# 2_-_Connector_Page.net
KiCad netlist of a schematic drawn in Altium Designer
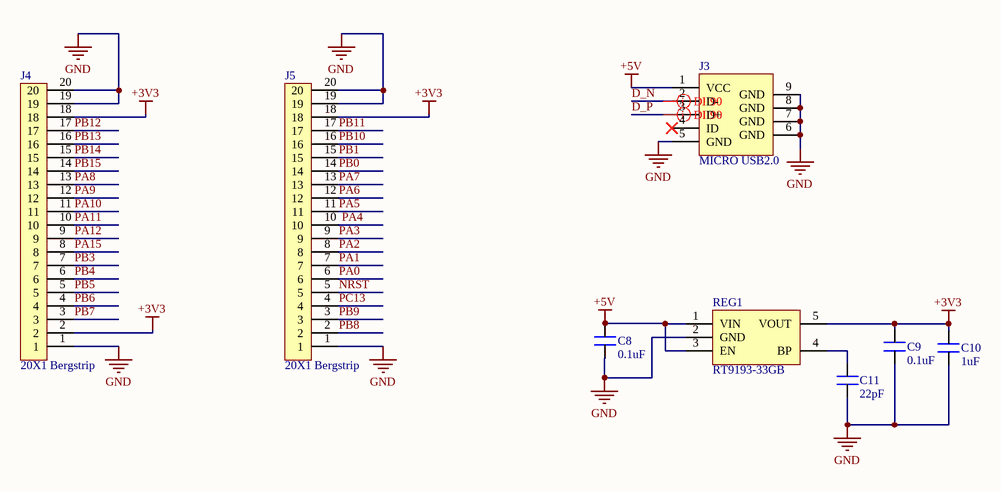
[diagram p0: [2]- Connector_Page.SchDoc]

(export (version "E")
  (design (tool "Eeschema 10.0.6"))
  (components
    (comp (ref "C8")
      (value "0.1uF")
      (footprint "CAP_0805")
      (description "0.1µF ±5% 50V Ceramic Capacitor X7R 0805 (2012 Metric)")
      (fields
        (field (name "MANUFACTURER") "KEMET")
        (field (name "MANUFACTURING PART NUMBER") "C0805C104J5RACTU")
      )
      (libsource (lib "STM_SCH_LIB") (part "CAP_0.1uF-50V-5%-0805"))
    )
    (comp (ref "C9")
      (value "0.1uF")
      (footprint "CAP_0805")
      (description "0.1µF ±5% 50V Ceramic Capacitor X7R 0805 (2012 Metric)")
      (fields
        (field (name "MANUFACTURER") "KEMET")
        (field (name "MANUFACTURING PART NUMBER") "C0805C104J5RACTU")
      )
      (libsource (lib "STM_SCH_LIB") (part "CAP_0.1uF-50V-5%-0805"))
    )
    (comp (ref "C10")
      (value "1uF")
      (footprint "CAP_0805")
      (description "1µF ±5% 50V Ceramic Capacitor X7R 0805 (2012 Metric)")
      (fields
        (field (name "MANUFACTURER") "Yageo")
        (field (name "MANUFACTURING PART NUMBER") "CC0805JKX7R9BB105")
      )
      (libsource (lib "STM_SCH_LIB") (part "CAP_1uF-50V-5%-0805"))
    )
    (comp (ref "C11")
      (value "22pF")
      (footprint "CAP_0805")
      (description "22pF ±5% 50V Ceramic Capacitor C0G, NP0 0805 (2012 Metric)")
      (fields
        (field (name "MANUFACTURER") "KEMET")
        (field (name "MANUFACTURER PART NUMBER") "C0805C220J5GACTU")
      )
      (libsource (lib "STM_SCH_LIB") (part "CAP_22pF-50V-5%-0805"))
    )
    (comp (ref "J3")
      (value "MICRO USB2.0")
      (footprint "CON_10118192-0001LF_SMD")
      (description "USB - micro B USB 2.0 Receptacle Connector 5 Position Surface Mount, Right Angle")
      (fields
        (field (name "MANUFACTURER") "Amphenol ICC (FCI)")
        (field (name "MANUFACTURING PART NUMBER") "10118192-0002LF")
      )
      (libsource (lib "STM_SCH_LIB") (part "CON-USB_10118192-0002LF-SMD"))
    )
    (comp (ref "J4")
      (value "20X1 Bergstrip")
      (footprint "CON20_100_40D72_TH_ST")
      (description "20 pin, 1 row, 2.54mm pitch bergstrip")
      (fields (field (name "MANUFACTURER") "NA"))
      (libsource (lib "STM_SCH_LIB") (part "CON-BS-PLG_20X1-100-TH-ST"))
    )
    (comp (ref "J5")
      (value "20X1 Bergstrip")
      (footprint "CON20_100_40D72_TH_ST")
      (description "20 pin, 1 row, 2.54mm pitch bergstrip")
      (fields (field (name "MANUFACTURER") "NA"))
      (libsource (lib "STM_SCH_LIB") (part "CON-BS-PLG_20X1-100-TH-ST"))
    )
    (comp (ref "REG1")
      (value "RT9193-33GB")
      (footprint "SOT23-5")
      (description "Linear Voltage Regulator IC 1 Output 300mA SOT-23-5")
      (fields (field (name "MANUFACTURER") "Richtek USA Inc."))
      (libsource (lib "STM_SCH_LIB") (part "REG_3.3V-5.5V-0.3A-SOT-23-5"))
    )
  )
  (nets
    (net (code "1") (name "+3V3") (class "Default")
      (node (ref "C10") (pin "2") (pinfunction "2_2") (pintype "passive"))
      (node (ref "C9") (pin "2") (pinfunction "2_2") (pintype "passive"))
      (node (ref "J4") (pin "18") (pinfunction "18_18") (pintype "passive"))
      (node (ref "J4") (pin "2") (pinfunction "2_2") (pintype "passive"))
      (node (ref "J5") (pin "18") (pinfunction "18_18") (pintype "passive"))
      (node (ref "REG1") (pin "5") (pinfunction "VOUT_5") (pintype "passive"))
    )
    (net (code "2") (name "+5V") (class "Default")
      (node (ref "C8") (pin "2") (pinfunction "2_2") (pintype "passive"))
      (node (ref "J3") (pin "1") (pinfunction "VCC_1") (pintype "passive"))
      (node (ref "REG1") (pin "1") (pinfunction "VIN_1") (pintype "passive"))
      (node (ref "REG1") (pin "3") (pinfunction "EN_3") (pintype "passive"))
    )
    (net (code "3") (name "/D_N") (class "Default")
      (node (ref "J3") (pin "2") (pinfunction "D-_2") (pintype "passive"))
    )
    (net (code "4") (name "/D_P") (class "Default")
      (node (ref "J3") (pin "3") (pinfunction "D+_3") (pintype "passive"))
    )
    (net (code "5") (name "/NRST") (class "Default")
      (node (ref "J5") (pin "5") (pinfunction "5_5") (pintype "passive"))
    )
    (net (code "6") (name "/PA0") (class "Default")
      (node (ref "J5") (pin "6") (pinfunction "6_6") (pintype "passive"))
    )
    (net (code "7") (name "/PA1") (class "Default")
      (node (ref "J5") (pin "7") (pinfunction "7_7") (pintype "passive"))
    )
    (net (code "8") (name "/PA2") (class "Default")
      (node (ref "J5") (pin "8") (pinfunction "8_8") (pintype "passive"))
    )
    (net (code "9") (name "/PA3") (class "Default")
      (node (ref "J5") (pin "9") (pinfunction "9_9") (pintype "passive"))
    )
    (net (code "10") (name "/PA4") (class "Default")
      (node (ref "J5") (pin "10") (pinfunction "10_10") (pintype "passive"))
    )
    (net (code "11") (name "/PA5") (class "Default")
      (node (ref "J5") (pin "11") (pinfunction "11_11") (pintype "passive"))
    )
    (net (code "12") (name "/PA6") (class "Default")
      (node (ref "J5") (pin "12") (pinfunction "12_12") (pintype "passive"))
    )
    (net (code "13") (name "/PA7") (class "Default")
      (node (ref "J5") (pin "13") (pinfunction "13_13") (pintype "passive"))
    )
    (net (code "14") (name "/PA8") (class "Default")
      (node (ref "J4") (pin "13") (pinfunction "13_13") (pintype "passive"))
    )
    (net (code "15") (name "/PA9") (class "Default")
      (node (ref "J4") (pin "12") (pinfunction "12_12") (pintype "passive"))
    )
    (net (code "16") (name "/PA10") (class "Default")
      (node (ref "J4") (pin "11") (pinfunction "11_11") (pintype "passive"))
    )
    (net (code "17") (name "/PA11") (class "Default")
      (node (ref "J4") (pin "10") (pinfunction "10_10") (pintype "passive"))
    )
    (net (code "18") (name "/PA12") (class "Default")
      (node (ref "J4") (pin "9") (pinfunction "9_9") (pintype "passive"))
    )
    (net (code "19") (name "/PA15") (class "Default")
      (node (ref "J4") (pin "8") (pinfunction "8_8") (pintype "passive"))
    )
    (net (code "20") (name "/PB0") (class "Default")
      (node (ref "J5") (pin "14") (pinfunction "14_14") (pintype "passive"))
    )
    (net (code "21") (name "/PB1") (class "Default")
      (node (ref "J5") (pin "15") (pinfunction "15_15") (pintype "passive"))
    )
    (net (code "22") (name "/PB3") (class "Default")
      (node (ref "J4") (pin "7") (pinfunction "7_7") (pintype "passive"))
    )
    (net (code "23") (name "/PB4") (class "Default")
      (node (ref "J4") (pin "6") (pinfunction "6_6") (pintype "passive"))
    )
    (net (code "24") (name "/PB5") (class "Default")
      (node (ref "J4") (pin "5") (pinfunction "5_5") (pintype "passive"))
    )
    (net (code "25") (name "/PB6") (class "Default")
      (node (ref "J4") (pin "4") (pinfunction "4_4") (pintype "passive"))
    )
    (net (code "26") (name "/PB7") (class "Default")
      (node (ref "J4") (pin "3") (pinfunction "3_3") (pintype "passive"))
    )
    (net (code "27") (name "/PB8") (class "Default")
      (node (ref "J5") (pin "2") (pinfunction "2_2") (pintype "passive"))
    )
    (net (code "28") (name "/PB9") (class "Default")
      (node (ref "J5") (pin "3") (pinfunction "3_3") (pintype "passive"))
    )
    (net (code "29") (name "/PB10") (class "Default")
      (node (ref "J5") (pin "16") (pinfunction "16_16") (pintype "passive"))
    )
    (net (code "30") (name "/PB11") (class "Default")
      (node (ref "J5") (pin "17") (pinfunction "17_17") (pintype "passive"))
    )
    (net (code "31") (name "/PB12") (class "Default")
      (node (ref "J4") (pin "17") (pinfunction "17_17") (pintype "passive"))
    )
    (net (code "32") (name "/PB13") (class "Default")
      (node (ref "J4") (pin "16") (pinfunction "16_16") (pintype "passive"))
    )
    (net (code "33") (name "/PB14") (class "Default")
      (node (ref "J4") (pin "15") (pinfunction "15_15") (pintype "passive"))
    )
    (net (code "34") (name "/PB15") (class "Default")
      (node (ref "J4") (pin "14") (pinfunction "14_14") (pintype "passive"))
    )
    (net (code "35") (name "/PC13") (class "Default")
      (node (ref "J5") (pin "4") (pinfunction "4_4") (pintype "passive"))
    )
    (net (code "36") (name "GND") (class "Default")
      (node (ref "C10") (pin "1") (pinfunction "1_1") (pintype "passive"))
      (node (ref "C11") (pin "1") (pinfunction "1_1") (pintype "passive"))
      (node (ref "C8") (pin "1") (pinfunction "1_1") (pintype "passive"))
      (node (ref "C9") (pin "1") (pinfunction "1_1") (pintype "passive"))
      (node (ref "J3") (pin "5") (pinfunction "GND_5") (pintype "passive"))
      (node (ref "J3") (pin "6") (pinfunction "GND_6") (pintype "passive"))
      (node (ref "J3") (pin "7") (pinfunction "GND_7") (pintype "passive"))
      (node (ref "J3") (pin "8") (pinfunction "GND_8") (pintype "passive"))
      (node (ref "J3") (pin "9") (pinfunction "GND_9") (pintype "passive"))
      (node (ref "J4") (pin "1") (pinfunction "1_1") (pintype "passive"))
      (node (ref "J4") (pin "19") (pinfunction "19_19") (pintype "passive"))
      (node (ref "J4") (pin "20") (pinfunction "20_20") (pintype "passive"))
      (node (ref "J5") (pin "1") (pinfunction "1_1") (pintype "passive"))
      (node (ref "J5") (pin "19") (pinfunction "19_19") (pintype "passive"))
      (node (ref "J5") (pin "20") (pinfunction "20_20") (pintype "passive"))
      (node (ref "REG1") (pin "2") (pinfunction "GND_2") (pintype "passive"))
    )
    (net (code "37") (name "Net-(REG1-BP)") (class "Default")
      (node (ref "C11") (pin "2") (pinfunction "2_2") (pintype "passive"))
      (node (ref "REG1") (pin "4") (pinfunction "BP_4") (pintype "passive"))
    )
    (net (code "38") (name "unconnected-(J3-ID-Pad4)") (class "Default")
      (node (ref "J3") (pin "4") (pinfunction "ID_4") (pintype "passive+no_connect"))
    )
  )
)
